# Main.net
KiCad netlist of a schematic drawn in Altium Designer
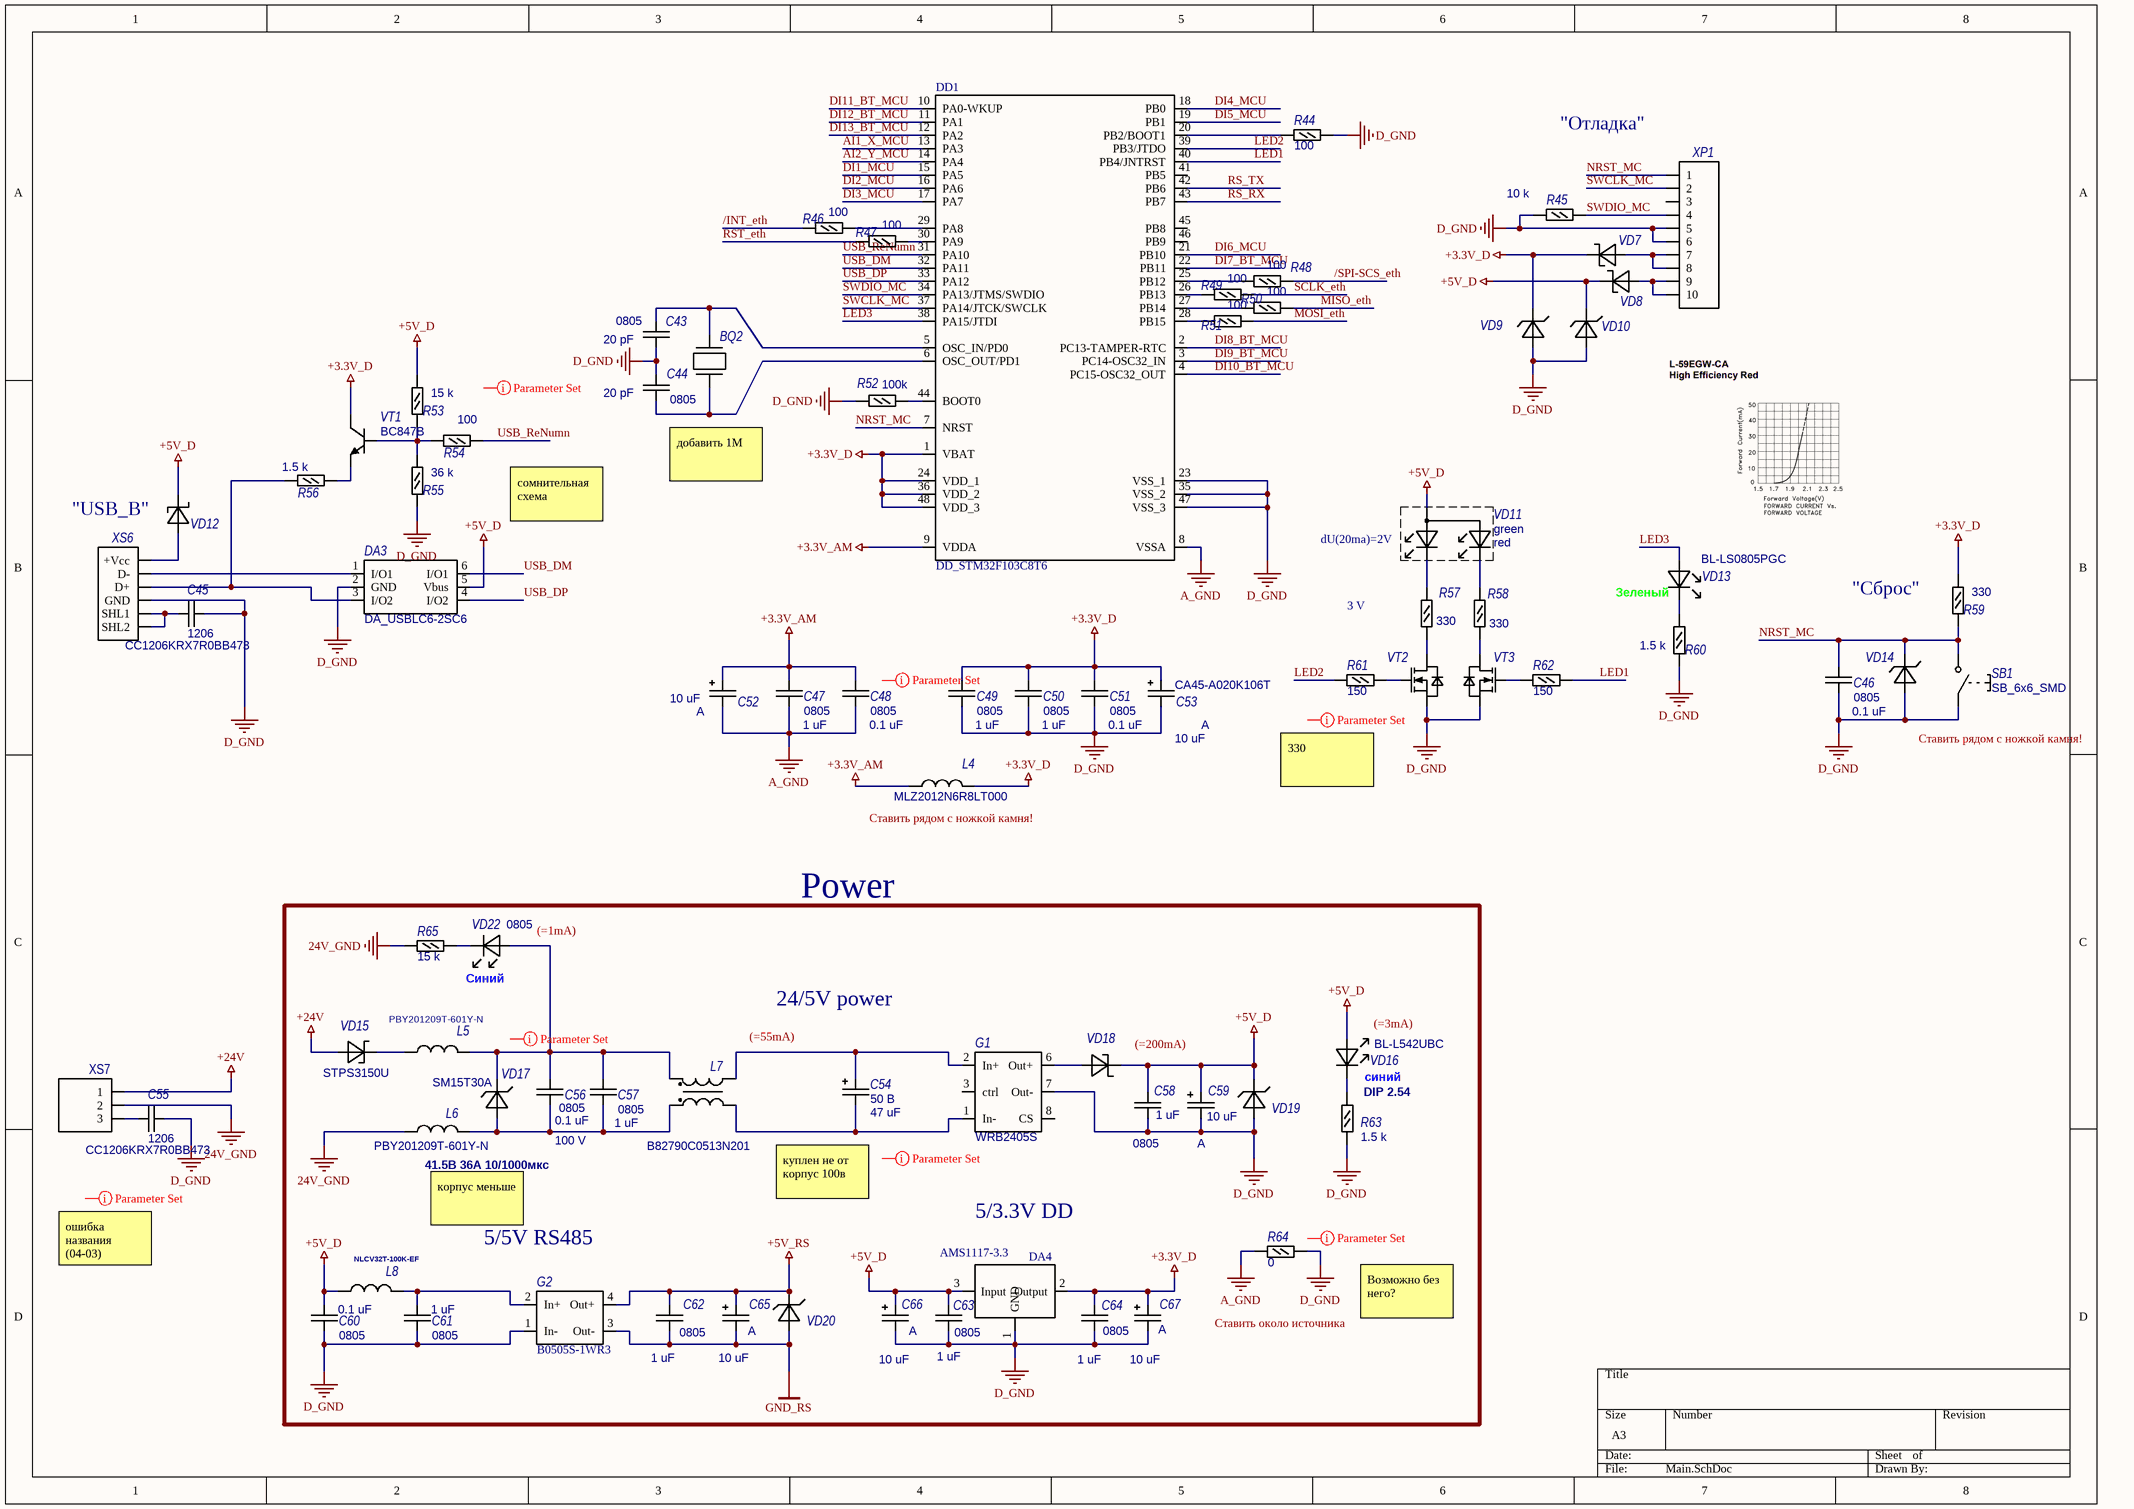
[diagram p0: Main.SchDoc]

(export (version "E")
  (design (tool "Eeschema 10.0.6"))
  (components
    (comp (ref "BQ2") (value "~") (footprint "Xtal_HC49S") (libsource (lib "Privod_A_K") (part "Xtal")))
    (comp (ref "C43")
      (value "0805")
      (footprint "CAP_0805_(2x1.25x1.3)")
      (description "Керамика")
      (fields (field (name "НОМИНАЛ") "20 pF"))
      (libsource (lib "Privod_A_K") (part "C_0805"))
    )
    (comp (ref "C44")
      (value "0805")
      (footprint "CAP_0805_(2x1.25x1.3)")
      (description "Керамика")
      (fields (field (name "НОМИНАЛ") "20 pF"))
      (libsource (lib "Privod_A_K") (part "C_0805"))
    )
    (comp (ref "C45")
      (value "1206")
      (footprint "CAP_1206_(3.2x1.6x1.5)")
      (description "Керамика")
      (fields (field (name "НАИМЕНОВАНИЕ") "CC1206KRX7R0BB473"))
      (libsource (lib "Privod_A_K") (part "C_1206"))
    )
    (comp (ref "C46")
      (value "0805")
      (footprint "CAP_0805_(2x1.25x1.3)")
      (description "Керамика")
      (fields (field (name "НОМИНАЛ") "0.1 uF"))
      (libsource (lib "Privod_A_K") (part "C_0805"))
    )
    (comp (ref "C47")
      (value "0805")
      (footprint "CAP_0805_(2x1.25x1.3)")
      (description "Керамика")
      (fields (field (name "НОМИНАЛ") "1 uF"))
      (libsource (lib "Privod_A_K") (part "C_0805"))
    )
    (comp (ref "C48")
      (value "0805")
      (footprint "CAP_0805_(2x1.25x1.3)")
      (description "Керамика")
      (fields (field (name "НОМИНАЛ") "0.1 uF"))
      (libsource (lib "Privod_A_K") (part "C_0805"))
    )
    (comp (ref "C49")
      (value "0805")
      (footprint "CAP_0805_(2x1.25x1.3)")
      (description "Керамика")
      (fields (field (name "НОМИНАЛ") "1 uF"))
      (libsource (lib "Privod_A_K") (part "C_0805"))
    )
    (comp (ref "C50")
      (value "0805")
      (footprint "CAP_0805_(2x1.25x1.3)")
      (description "Керамика")
      (fields (field (name "НОМИНАЛ") "1 uF"))
      (libsource (lib "Privod_A_K") (part "C_0805"))
    )
    (comp (ref "C51")
      (value "0805")
      (footprint "CAP_0805_(2x1.25x1.3)")
      (description "Керамика")
      (fields (field (name "НОМИНАЛ") "0.1 uF"))
      (libsource (lib "Privod_A_K") (part "C_0805"))
    )
    (comp (ref "C52")
      (value "TAN_A")
      (footprint "CAP_TAN_A")
      (description "Capacitor")
      (fields (field (name "КОРПУС") "A") (field (name "НОМИНАЛ") "10 uF"))
      (libsource (lib "Privod_A_K") (part "C+_TAN_A"))
    )
    (comp (ref "C53")
      (value "TAN_A")
      (footprint "CAP_TAN_A")
      (description "Capacitor")
      (fields
        (field (name "КОРПУС") "A")
        (field (name "НАИМЕНОВАНИЕ") "CA45-A020K106T")
        (field (name "НОМИНАЛ") "10 uF")
      )
      (libsource (lib "Privod_A_K") (part "C+_TAN_A"))
    )
    (comp (ref "C54")
      (value "K50-35")
      (footprint "CAP_EL_K50-35_(8x11.5)")
      (description "Capacitor")
      (fields (field (name "НАПРЯЖЕНИЕ") "50 В") (field (name "НОМИНАЛ") "47 uF"))
      (libsource (lib "Privod_A_K") (part "C+_K50-35_(8x11.5)"))
    )
    (comp (ref "C55")
      (value "1206")
      (footprint "CAP_1206_(3.2x1.6x1.5)")
      (description "Керамика")
      (fields (field (name "НАИМЕНОВАНИЕ") "CC1206KRX7R0BB473"))
      (libsource (lib "Privod_A_K") (part "C_1206"))
    )
    (comp (ref "C56")
      (value "0805")
      (footprint "CAP_0805_(2x1.25x1.3)")
      (description "Керамика")
      (fields (field (name "НАПРЯЖЕНИЕ") "100 V") (field (name "НОМИНАЛ") "0.1 uF"))
      (libsource (lib "Privod_A_K") (part "C_0805"))
    )
    (comp (ref "C57")
      (value "0805")
      (footprint "CAP_0805_(2x1.25x1.3)")
      (description "Керамика")
      (fields (field (name "НОМИНАЛ") "1 uF"))
      (libsource (lib "Privod_A_K") (part "C_0805"))
    )
    (comp (ref "C58")
      (value "0805")
      (footprint "CAP_0805_(2x1.25x1.3)")
      (description "Керамика")
      (fields (field (name "НОМИНАЛ") "1 uF"))
      (libsource (lib "Privod_A_K") (part "C_0805"))
    )
    (comp (ref "C59")
      (value "TAN_A")
      (footprint "CAP_TAN_A")
      (description "Capacitor")
      (fields (field (name "КОРПУС") "A") (field (name "НОМИНАЛ") "10 uF"))
      (libsource (lib "Privod_A_K") (part "C+_TAN_A"))
    )
    (comp (ref "C60")
      (value "0805")
      (footprint "CAP_0805_(2x1.25x1.3)")
      (description "Керамика")
      (fields (field (name "НОМИНАЛ") "0.1 uF"))
      (libsource (lib "Privod_A_K") (part "C_0805"))
    )
    (comp (ref "C61")
      (value "0805")
      (footprint "CAP_0805_(2x1.25x1.3)")
      (description "Керамика")
      (fields (field (name "НОМИНАЛ") "1 uF"))
      (libsource (lib "Privod_A_K") (part "C_0805"))
    )
    (comp (ref "C62")
      (value "0805")
      (footprint "CAP_0805_(2x1.25x1.3)")
      (description "Керамика")
      (fields (field (name "НОМИНАЛ") "1 uF"))
      (libsource (lib "Privod_A_K") (part "C_0805"))
    )
    (comp (ref "C63")
      (value "0805")
      (footprint "CAP_0805_(2x1.25x1.3)")
      (description "Керамика")
      (fields (field (name "НОМИНАЛ") "1 uF"))
      (libsource (lib "Privod_A_K") (part "C_0805"))
    )
    (comp (ref "C64")
      (value "0805")
      (footprint "CAP_0805_(2x1.25x1.3)")
      (description "Керамика")
      (fields (field (name "НОМИНАЛ") "1 uF"))
      (libsource (lib "Privod_A_K") (part "C_0805"))
    )
    (comp (ref "C65")
      (value "TAN_A")
      (footprint "CAP_TAN_A")
      (description "Capacitor")
      (fields (field (name "КОРПУС") "A") (field (name "НОМИНАЛ") "10 uF"))
      (libsource (lib "Privod_A_K") (part "C+_TAN_A"))
    )
    (comp (ref "C66")
      (value "TAN_A")
      (footprint "CAP_TAN_A")
      (description "Capacitor")
      (fields (field (name "КОРПУС") "A") (field (name "НОМИНАЛ") "10 uF"))
      (libsource (lib "Privod_A_K") (part "C+_TAN_A"))
    )
    (comp (ref "C67")
      (value "TAN_A")
      (footprint "CAP_TAN_A")
      (description "Capacitor")
      (fields (field (name "КОРПУС") "A") (field (name "НОМИНАЛ") "10 uF"))
      (libsource (lib "Privod_A_K") (part "C+_TAN_A"))
    )
    (comp (ref "DA3")
      (value "DA_USBLC6-2SC6")
      (footprint "SOT-23-6L")
      (description "USB ESD protector SOT23-6")
      (libsource (lib "Privod_A_K") (part "DA_USBLC6-2SC6"))
    )
    (comp (ref "DA4")
      (value "AMS1117-3.3")
      (footprint "SOT-223_Dupl")
      (description "0.8A Low Dropout Voltage Regulator       SOT 223")
      (libsource (lib "Privod_A_K") (part "DA_AMS1117-3.3"))
    )
    (comp (ref "DD1")
      (value "DD_STM32F103C8T6")
      (footprint "LQFP_48")
      (description "STM32 ARM-based 32-bit MCU with 128 Kbytes Flash, 48-pin LQFP, Industrial Temperature")
      (fields (field (name "PUBLISHER") "Altium Limited"))
      (libsource (lib "Privod_A_K") (part "DD_STM32F103C8T6"))
    )
    (comp (ref "G1")
      (value "WRB2405S")
      (footprint "WRB2405S(SIP-8) - duplicate")
      (description "DC/DC")
      (libsource (lib "Privod_A_K") (part "G_WRB2405S-1WR2"))
    )
    (comp (ref "G2")
      (value "AM1S-Z")
      (footprint "AM1S-Z")
      (description "DC/DC")
      (fields (field (name "НАИМЕНОВАНИЕ") "B0505S-1WR3"))
      (libsource (lib "Privod_A_K") (part "G_AM1S-Z"))
    )
    (comp (ref "L4")
      (value "PBY201209T-601Y-N")
      (footprint "L_0805")
      (description "L")
      (fields (field (name "НАИМЕНОВАНИЕ") "MLZ2012N6R8LT000"))
      (libsource (lib "Privod_A_K") (part "L_PBY201209T-601Y-N"))
    )
    (comp (ref "L5")
      (value "PBY201209T-601Y-N")
      (footprint "L_0805")
      (description "L")
      (libsource (lib "Privod_A_K") (part "L_PBY201209T-601Y-N"))
    )
    (comp (ref "L6")
      (value "PBY201209T-601Y-N")
      (footprint "L_0805")
      (description "L")
      (libsource (lib "Privod_A_K") (part "L_PBY201209T-601Y-N"))
    )
    (comp (ref "L7")
      (value "B82790")
      (footprint "B82790")
      (description "L")
      (fields (field (name "НАИМЕНОВАНИЕ") "B82790C0513N201"))
      (libsource (lib "Privod_A_K") (part "L_B82790"))
    )
    (comp (ref "L8")
      (value "SRN3015")
      (footprint "L_SRN3015")
      (description "L")
      (fields (field (name "НАИМЕНОВАНИЕ") "NLCV32T-100K-EF"))
      (libsource (lib "Privod_A_K") (part "L_SRN3015"))
    )
    (comp (ref "R44")
      (value "0805")
      (footprint "RES_0805_(2x1.2x0.45)_0.125Вт")
      (description "Resistor")
      (fields (field (name "НОМИНАЛ") "100"))
      (libsource (lib "") (part "R_0805_2"))
    )
    (comp (ref "R45")
      (value "0805")
      (footprint "RES_0805_(2x1.2x0.45)_0.125Вт")
      (description "Resistor")
      (fields (field (name "НОМИНАЛ") "10 k"))
      (libsource (lib "") (part "R_0805_2"))
    )
    (comp (ref "R46")
      (value "0805")
      (footprint "RES_0805_(2x1.2x0.45)_0.125Вт")
      (description "Resistor")
      (fields (field (name "НОМИНАЛ") "100"))
      (libsource (lib "") (part "R_0805_2"))
    )
    (comp (ref "R47")
      (value "0805")
      (footprint "RES_0805_(2x1.2x0.45)_0.125Вт")
      (description "Resistor")
      (fields (field (name "НОМИНАЛ") "100"))
      (libsource (lib "") (part "R_0805_2"))
    )
    (comp (ref "R48")
      (value "0805")
      (footprint "RES_0805_(2x1.2x0.45)_0.125Вт")
      (description "Resistor")
      (fields (field (name "НОМИНАЛ") "100"))
      (libsource (lib "") (part "R_0805_2"))
    )
    (comp (ref "R49")
      (value "0805")
      (footprint "RES_0805_(2x1.2x0.45)_0.125Вт")
      (description "Resistor")
      (fields (field (name "НОМИНАЛ") "100"))
      (libsource (lib "") (part "R_0805_2"))
    )
    (comp (ref "R50")
      (value "0805")
      (footprint "RES_0805_(2x1.2x0.45)_0.125Вт")
      (description "Resistor")
      (fields (field (name "НОМИНАЛ") "100"))
      (libsource (lib "") (part "R_0805_2"))
    )
    (comp (ref "R51")
      (value "0805")
      (footprint "RES_0805_(2x1.2x0.45)_0.125Вт")
      (description "Resistor")
      (fields (field (name "НОМИНАЛ") "100"))
      (libsource (lib "") (part "R_0805_2"))
    )
    (comp (ref "R52")
      (value "0805")
      (footprint "RES_0805_(2x1.2x0.45)_0.125Вт")
      (description "Resistor")
      (fields (field (name "НОМИНАЛ") "100k"))
      (libsource (lib "") (part "R_0805_2"))
    )
    (comp (ref "R53")
      (value "0805")
      (footprint "RES_0805_(2x1.2x0.45)_0.125Вт")
      (description "Resistor")
      (fields (field (name "НОМИНАЛ") "15 k"))
      (libsource (lib "") (part "R_0805_1"))
    )
    (comp (ref "R54")
      (value "0805")
      (footprint "RES_0805_(2x1.2x0.45)_0.125Вт")
      (description "Resistor")
      (fields (field (name "НОМИНАЛ") "100"))
      (libsource (lib "") (part "R_0805_2"))
    )
    (comp (ref "R55")
      (value "0805")
      (footprint "RES_0805_(2x1.2x0.45)_0.125Вт")
      (description "Resistor")
      (fields (field (name "НОМИНАЛ") "36 k"))
      (libsource (lib "") (part "R_0805_1"))
    )
    (comp (ref "R56")
      (value "0805")
      (footprint "RES_0805_(2x1.2x0.45)_0.125Вт")
      (description "Resistor")
      (fields (field (name "НОМИНАЛ") "1.5 k"))
      (libsource (lib "") (part "R_0805_2"))
    )
    (comp (ref "R57")
      (value "0805")
      (footprint "RES_0805_(2x1.2x0.45)_0.125Вт")
      (description "Resistor")
      (fields (field (name "НОМИНАЛ") "330"))
      (libsource (lib "") (part "R_0805_3"))
    )
    (comp (ref "R58")
      (value "0805")
      (footprint "RES_0805_(2x1.2x0.45)_0.125Вт")
      (description "Resistor")
      (fields (field (name "НОМИНАЛ") "330"))
      (libsource (lib "") (part "R_0805_3"))
    )
    (comp (ref "R59")
      (value "0805")
      (footprint "RES_0805_(2x1.2x0.45)_0.125Вт")
      (description "Resistor")
      (fields (field (name "НОМИНАЛ") "330"))
      (libsource (lib "") (part "R_0805_3"))
    )
    (comp (ref "R60")
      (value "0805")
      (footprint "RES_0805_(2x1.2x0.45)_0.125Вт")
      (description "Resistor")
      (fields (field (name "НОМИНАЛ") "1.5 k"))
      (libsource (lib "") (part "R_0805_1"))
    )
    (comp (ref "R61")
      (value "0805")
      (footprint "RES_0805_(2x1.2x0.45)_0.125Вт")
      (description "Resistor")
      (fields (field (name "НОМИНАЛ") "150"))
      (libsource (lib "Privod_A_K") (part "R_0805"))
    )
    (comp (ref "R62")
      (value "0805")
      (footprint "RES_0805_(2x1.2x0.45)_0.125Вт")
      (description "Resistor")
      (fields (field (name "НОМИНАЛ") "150"))
      (libsource (lib "Privod_A_K") (part "R_0805"))
    )
    (comp (ref "R63")
      (value "0805")
      (footprint "RES_0805_(2x1.2x0.45)_0.125Вт")
      (description "Resistor")
      (fields (field (name "НОМИНАЛ") "1.5 k"))
      (libsource (lib "") (part "R_0805_1"))
    )
    (comp (ref "R64")
      (value "0805")
      (footprint "RES_0805_(2x1.2x0.45)_0.125Вт")
      (description "Resistor")
      (fields (field (name "НОМИНАЛ") "0"))
      (libsource (lib "Privod_A_K") (part "R_0805"))
    )
    (comp (ref "R65")
      (value "0805")
      (footprint "RES_0805_(2x1.2x0.45)_0.125Вт")
      (description "Resistor")
      (fields (field (name "НОМИНАЛ") "15 k"))
      (libsource (lib "Privod_A_K") (part "R_0805"))
    )
    (comp (ref "SB1")
      (value "SB_6x6_SMD")
      (footprint "SB_6x6_SMD")
      (libsource (lib "Privod_A_K") (part "SB_6x6_SMD"))
    )
    (comp (ref "VD7")
      (value "VD_SH_SMA")
      (footprint "VD_SMA_(Do-214AC)")
      (description "Sh_Diode")
      (libsource (lib "Privod_A_K") (part "VD_SH_SMA"))
    )
    (comp (ref "VD8")
      (value "VD_SH_SMA")
      (footprint "VD_SMA_(Do-214AC)")
      (description "Sh_Diode")
      (libsource (lib "Privod_A_K") (part "VD_SH_SMA"))
    )
    (comp (ref "VD9")
      (value "ESD")
      (footprint "VD_SOD523")
      (description "Защитный диод")
      (libsource (lib "Privod_A_K") (part "VD_ESD"))
    )
    (comp (ref "VD10")
      (value "ESD")
      (footprint "VD_SOD523")
      (description "Защитный диод")
      (libsource (lib "Privod_A_K") (part "VD_ESD"))
    )
    (comp (ref "VD11")
      (value "VD_Ledx2_dip")
      (footprint "VD_LEDsx2")
      (fields (field (name "ТИП") "green") (field (name "ПРИМЕЧАНИЯ") "red"))
      (libsource (lib "Privod_A_K") (part "VD_Ledx2_dip"))
    )
    (comp (ref "VD12")
      (value "VD_SH_SMA")
      (footprint "VD_SMA_(Do-214AC)")
      (description "Sh_Diode")
      (libsource (lib "Privod_A_K") (part "VD_SH_SMA"))
    )
    (comp (ref "VD13")
      (value "VD_Led_0805")
      (footprint "led_0805")
      (fields (field (name "НАИМЕНОВАНИЕ") "BL-LS0805PGC") (field (name "ПРИМЕЧАНИЯ") "Зеленый"))
      (libsource (lib "Privod_A_K") (part "VD_Led_0805"))
    )
    (comp (ref "VD14")
      (value "ESD")
      (footprint "VD_SOD523")
      (description "Защитный диод")
      (libsource (lib "Privod_A_K") (part "VD_ESD"))
    )
    (comp (ref "VD15")
      (value "STPS3150U")
      (footprint "VD_SMB_(Do-214AA)")
      (description "Диод Шоттки 150В 3А [SMB]")
      (libsource (lib "Privod_A_K") (part "VD_STPS3150U"))
    )
    (comp (ref "VD16")
      (value "VD_Led")
      (footprint "VD_LED_dip")
      (fields
        (field (name "КОРПУС") "DIP 2.54")
        (field (name "НАИМЕНОВАНИЕ") "BL-L542UBC")
        (field (name "ПРИМЕЧАНИЯ") "синий")
      )
      (libsource (lib "Privod_A_K") (part "VD_Led"))
    )
    (comp (ref "VD17")
      (value "SM15T30A")
      (footprint "VD_SMC_(Do-214AB)")
      (description "Защитный диод 48В")
      (fields (field (name "НОМИНАЛ") " 41.5В 36А 10/1000мкс"))
      (libsource (lib "Privod_A_K") (part "VD_SMCJ48A"))
    )
    (comp (ref "VD18")
      (value "VD_SH_SMA")
      (footprint "VD_SMA_(Do-214AC)")
      (description "Sh_Diode")
      (libsource (lib "Privod_A_K") (part "VD_SH_SMA"))
    )
    (comp (ref "VD19")
      (value "VD_SMA")
      (footprint "VD_SMA_(Do-214AC)")
      (description "Diode")
      (libsource (lib "Privod_A_K") (part "VD_SMA"))
    )
    (comp (ref "VD20")
      (value "VD_SMA")
      (footprint "VD_SMA_(Do-214AC)")
      (description "Diode")
      (libsource (lib "Privod_A_K") (part "VD_SMA"))
    )
    (comp (ref "VD22")
      (value "VD_Led_0805")
      (footprint "led_0805")
      (fields (field (name "КОРПУС") "0805") (field (name "ПРИМЕЧАНИЯ") "Синий"))
      (libsource (lib "Privod_A_K") (part "VD_Led_0805"))
    )
    (comp (ref "VT1")
      (value "BC847B")
      (footprint "SOT-23")
      (description "NPN Bipolar Transistor")
      (libsource (lib "Privod_A_K") (part "VT_BC847B"))
    )
    (comp (ref "VT2")
      (value "VT_IRLML0040TRPBF")
      (footprint "SOT-23")
      (description "N Mosfet 3.6A")
      (libsource (lib "Privod_A_K") (part "VT_IRLML0040TRPBF"))
    )
    (comp (ref "VT3")
      (value "VT_IRLML0040TRPBF")
      (footprint "SOT-23")
      (description "N Mosfet 3.6A")
      (libsource (lib "Privod_A_K") (part "VT_IRLML0040TRPBF"))
    )
    (comp (ref "XP1")
      (value "XP_5x2_V")
      (footprint "XP_5x2_PIN_V")
      (libsource (lib "Privod_A_K") (part "XP_5x2_V"))
    )
    (comp (ref "XS6")
      (value "XS_USB_B")
      (footprint "XS_USBB")
      (libsource (lib "Privod_A_K") (part "XS_USB_B"))
    )
    (comp (ref "XS7")
      (value "XS_3_pin_3.8mm")
      (footprint "XS_3_Pin _3.8mm")
      (libsource (lib "Privod_A_K") (part "XS_3_pin_3.8mm"))
    )
  )
  (nets
    (net (code "1") (name "+3.3V_AM") (class "Default")
      (node (ref "C47") (pin "2") (pinfunction "2_2") (pintype "passive"))
      (node (ref "C48") (pin "2") (pinfunction "2_2") (pintype "passive"))
      (node (ref "C52") (pin "1") (pinfunction "1_1") (pintype "passive"))
      (node (ref "DD1") (pin "9") (pinfunction "VDDA_9") (pintype "passive"))
      (node (ref "L4") (pin "1") (pinfunction "1_1") (pintype "passive"))
    )
    (net (code "2") (name "+3.3V_D") (class "Default")
      (node (ref "C49") (pin "2") (pinfunction "2_2") (pintype "passive"))
      (node (ref "C50") (pin "2") (pinfunction "2_2") (pintype "passive"))
      (node (ref "C51") (pin "2") (pinfunction "2_2") (pintype "passive"))
      (node (ref "C53") (pin "1") (pinfunction "1_1") (pintype "passive"))
      (node (ref "C64") (pin "2") (pinfunction "2_2") (pintype "passive"))
      (node (ref "C67") (pin "1") (pinfunction "1_1") (pintype "passive"))
      (node (ref "DA4") (pin "2") (pinfunction "Output_2") (pintype "passive"))
      (node (ref "DD1") (pin "1") (pinfunction "VBAT_1") (pintype "passive"))
      (node (ref "DD1") (pin "24") (pinfunction "VDD_1_24") (pintype "passive"))
      (node (ref "DD1") (pin "36") (pinfunction "VDD_2_36") (pintype "passive"))
      (node (ref "DD1") (pin "48") (pinfunction "VDD_3_48") (pintype "passive"))
      (node (ref "L4") (pin "2") (pinfunction "2_2") (pintype "passive"))
      (node (ref "R59") (pin "1") (pinfunction "1_1") (pintype "passive"))
      (node (ref "VD7") (pin "2") (pinfunction "K_2") (pintype "passive"))
      (node (ref "VD9") (pin "2") (pinfunction "K_2") (pintype "passive"))
      (node (ref "VT1") (pin "3") (pinfunction "C_3") (pintype "passive"))
    )
    (net (code "3") (name "+5V_D") (class "Default")
      (node (ref "C58") (pin "2") (pinfunction "2_2") (pintype "passive"))
      (node (ref "C59") (pin "1") (pinfunction "1_1") (pintype "passive"))
      (node (ref "C60") (pin "2") (pinfunction "2_2") (pintype "passive"))
      (node (ref "C63") (pin "2") (pinfunction "2_2") (pintype "passive"))
      (node (ref "C66") (pin "1") (pinfunction "1_1") (pintype "passive"))
      (node (ref "DA3") (pin "5") (pinfunction "Vbus_5") (pintype "passive"))
      (node (ref "DA4") (pin "3") (pinfunction "Input_3") (pintype "passive"))
      (node (ref "L8") (pin "1") (pinfunction "1_1") (pintype "passive"))
      (node (ref "R53") (pin "2") (pinfunction "2_2") (pintype "passive"))
      (node (ref "VD10") (pin "2") (pinfunction "K_2") (pintype "passive"))
      (node (ref "VD11") (pin "2") (pinfunction "A_2") (pintype "passive"))
      (node (ref "VD12") (pin "2") (pinfunction "K_2") (pintype "passive"))
      (node (ref "VD16") (pin "1") (pinfunction "A_1") (pintype "passive"))
      (node (ref "VD18") (pin "2") (pinfunction "K_2") (pintype "passive"))
      (node (ref "VD19") (pin "2") (pinfunction "K_2") (pintype "passive"))
      (node (ref "VD8") (pin "2") (pinfunction "K_2") (pintype "passive"))
    )
    (net (code "4") (name "+5V_RS") (class "Default")
      (node (ref "C62") (pin "2") (pinfunction "2_2") (pintype "passive"))
      (node (ref "C65") (pin "1") (pinfunction "1_1") (pintype "passive"))
      (node (ref "G2") (pin "4") (pinfunction "Out+_4") (pintype "passive"))
      (node (ref "VD20") (pin "2") (pinfunction "K_2") (pintype "passive"))
    )
    (net (code "5") (name "+24V") (class "Default")
      (node (ref "VD15") (pin "1") (pinfunction "A_1") (pintype "passive"))
      (node (ref "XS7") (pin "1") (pinfunction "1_1") (pintype "passive"))
    )
    (net (code "6") (name "/AI1_X_MCU") (class "Default")
      (node (ref "DD1") (pin "13") (pinfunction "PA3_13") (pintype "passive"))
    )
    (net (code "7") (name "/AI2_Y_MCU") (class "Default")
      (node (ref "DD1") (pin "14") (pinfunction "PA4_14") (pintype "passive"))
    )
    (net (code "8") (name "/DI1_MCU") (class "Default")
      (node (ref "DD1") (pin "15") (pinfunction "PA5_15") (pintype "passive"))
    )
    (net (code "9") (name "/DI2_MCU") (class "Default")
      (node (ref "DD1") (pin "16") (pinfunction "PA6_16") (pintype "passive"))
    )
    (net (code "10") (name "/DI3_MCU") (class "Default")
      (node (ref "DD1") (pin "17") (pinfunction "PA7_17") (pintype "passive"))
    )
    (net (code "11") (name "/DI4_MCU") (class "Default")
      (node (ref "DD1") (pin "18") (pinfunction "PB0_18") (pintype "passive"))
    )
    (net (code "12") (name "/DI5_MCU") (class "Default")
      (node (ref "DD1") (pin "19") (pinfunction "PB1_19") (pintype "passive"))
    )
    (net (code "13") (name "/DI6_MCU") (class "Default")
      (node (ref "DD1") (pin "21") (pinfunction "PB10_21") (pintype "passive"))
    )
    (net (code "14") (name "/DI7_BT_MCU") (class "Default")
      (node (ref "DD1") (pin "22") (pinfunction "PB11_22") (pintype "passive"))
    )
    (net (code "15") (name "/DI8_BT_MCU") (class "Default")
      (node (ref "DD1") (pin "2") (pinfunction "PC13-TAMPER-RTC_2") (pintype "passive"))
    )
    (net (code "16") (name "/DI9_BT_MCU") (class "Default")
      (node (ref "DD1") (pin "3") (pinfunction "PC14-OSC32_IN_3") (pintype "passive"))
    )
    (net (code "17") (name "/DI10_BT_MCU") (class "Default")
      (node (ref "DD1") (pin "4") (pinfunction "PC15-OSC32_OUT_4") (pintype "passive"))
    )
    (net (code "18") (name "/DI11_BT_MCU") (class "Default")
      (node (ref "DD1") (pin "10") (pinfunction "PA0-WKUP_10") (pintype "passive"))
    )
    (net (code "19") (name "/DI12_BT_MCU") (class "Default")
      (node (ref "DD1") (pin "11") (pinfunction "PA1_11") (pintype "passive"))
    )
    (net (code "20") (name "/DI13_BT_MCU") (class "Default")
      (node (ref "DD1") (pin "12") (pinfunction "PA2_12") (pintype "passive"))
    )
    (net (code "21") (name "/LED1") (class "Default")
      (node (ref "DD1") (pin "40") (pinfunction "PB4/JNTRST_40") (pintype "passive"))
      (node (ref "R62") (pin "2") (pinfunction "2_2") (pintype "passive"))
    )
    (net (code "22") (name "/LED2") (class "Default")
      (node (ref "DD1") (pin "39") (pinfunction "PB3/JTDO_39") (pintype "passive"))
      (node (ref "R61") (pin "1") (pinfunction "1_1") (pintype "passive"))
    )
    (net (code "23") (name "/LED3") (class "Default")
      (node (ref "DD1") (pin "38") (pinfunction "PA15/JTDI_38") (pintype "passive"))
      (node (ref "VD13") (pin "1") (pinfunction "A_1") (pintype "passive"))
    )
    (net (code "24") (name "/MISO_eth") (class "Default")
      (node (ref "R50") (pin "1") (pinfunction "1_1") (pintype "passive"))
    )
    (net (code "25") (name "/MOSI_eth") (class "Default")
      (node (ref "R51") (pin "1") (pinfunction "1_1") (pintype "passive"))
    )
    (net (code "26") (name "/NRST_MC") (class "Default")
      (node (ref "C46") (pin "2") (pinfunction "2_2") (pintype "passive"))
      (node (ref "DD1") (pin "7") (pinfunction "NRST_7") (pintype "passive"))
      (node (ref "R59") (pin "2") (pinfunction "2_2") (pintype "passive"))
      (node (ref "SB1") (pin "2") (pinfunction "2_2") (pintype "passive"))
      (node (ref "VD14") (pin "2") (pinfunction "K_2") (pintype "passive"))
      (node (ref "XP1") (pin "1") (pinfunction "1_1") (pintype "passive"))
    )
    (net (code "27") (name "/RST_eth") (class "Default")
      (node (ref "R47") (pin "2") (pinfunction "2_2") (pintype "passive"))
    )
    (net (code "28") (name "/RS_RX") (class "Default")
      (node (ref "DD1") (pin "43") (pinfunction "PB7_43") (pintype "passive"))
    )
    (net (code "29") (name "/RS_TX") (class "Default")
      (node (ref "DD1") (pin "42") (pinfunction "PB6_42") (pintype "passive"))
    )
    (net (code "30") (name "/SCLK_eth") (class "Default")
      (node (ref "R49") (pin "1") (pinfunction "1_1") (pintype "passive"))
    )
    (net (code "31") (name "/SWCLK_MC") (class "Default")
      (node (ref "DD1") (pin "37") (pinfunction "PA14/JTCK/SWCLK_37") (pintype "passive"))
      (node (ref "XP1") (pin "2") (pinfunction "2_2") (pintype "passive"))
    )
    (net (code "32") (name "/SWDIO_MC") (class "Default")
      (node (ref "DD1") (pin "34") (pinfunction "PA13/JTMS/SWDIO_34") (pintype "passive"))
      (node (ref "R45") (pin "1") (pinfunction "1_1") (pintype "passive"))
      (node (ref "XP1") (pin "4") (pinfunction "4_4") (pintype "passive"))
    )
    (net (code "33") (name "/USB_DM") (class "Default")
      (node (ref "DA3") (pin "6") (pinfunction "I/O1_6") (pintype "passive"))
      (node (ref "DD1") (pin "32") (pinfunction "PA11_32") (pintype "passive"))
    )
    (net (code "34") (name "/USB_DP") (class "Default")
      (node (ref "DA3") (pin "4") (pinfunction "I/O2_4") (pintype "passive"))
      (node (ref "DD1") (pin "33") (pinfunction "PA12_33") (pintype "passive"))
    )
    (net (code "35") (name "/USB_ReNumn") (class "Default")
      (node (ref "DD1") (pin "31") (pinfunction "PA10_31") (pintype "passive"))
      (node (ref "R54") (pin "1") (pinfunction "1_1") (pintype "passive"))
    )
    (net (code "36") (name "/{slash}INT_eth") (class "Default")
      (node (ref "R46") (pin "2") (pinfunction "2_2") (pintype "passive"))
    )
    (net (code "37") (name "/{slash}SPI-SCS_eth") (class "Default")
      (node (ref "R48") (pin "1") (pinfunction "1_1") (pintype "passive"))
    )
    (net (code "38") (name "24V_GND") (class "Default")
      (node (ref "L6") (pin "1") (pinfunction "1_1") (pintype "passive"))
      (node (ref "R65") (pin "1") (pinfunction "1_1") (pintype "passive"))
      (node (ref "XS7") (pin "2") (pinfunction "2_2") (pintype "passive"))
    )
    (net (code "39") (name "A_GND") (class "Default")
      (node (ref "C47") (pin "1") (pinfunction "1_1") (pintype "passive"))
      (node (ref "C48") (pin "1") (pinfunction "1_1") (pintype "passive"))
      (node (ref "C52") (pin "2") (pinfunction "2_2") (pintype "passive"))
      (node (ref "DD1") (pin "8") (pinfunction "VSSA_8") (pintype "passive"))
      (node (ref "R64") (pin "1") (pinfunction "1_1") (pintype "passive"))
    )
    (net (code "40") (name "D_GND") (class "Default")
      (node (ref "C43") (pin "1") (pinfunction "1_1") (pintype "passive"))
      (node (ref "C44") (pin "2") (pinfunction "2_2") (pintype "passive"))
      (node (ref "C45") (pin "2") (pinfunction "2_2") (pintype "passive"))
      (node (ref "C46") (pin "1") (pinfunction "1_1") (pintype "passive"))
      (node (ref "C49") (pin "1") (pinfunction "1_1") (pintype "passive"))
      (node (ref "C50") (pin "1") (pinfunction "1_1") (pintype "passive"))
      (node (ref "C51") (pin "1") (pinfunction "1_1") (pintype "passive"))
      (node (ref "C53") (pin "2") (pinfunction "2_2") (pintype "passive"))
      (node (ref "C55") (pin "2") (pinfunction "2_2") (pintype "passive"))
      (node (ref "C58") (pin "1") (pinfunction "1_1") (pintype "passive"))
      (node (ref "C59") (pin "2") (pinfunction "2_2") (pintype "passive"))
      (node (ref "C60") (pin "1") (pinfunction "1_1") (pintype "passive"))
      (node (ref "C61") (pin "1") (pinfunction "1_1") (pintype "passive"))
      (node (ref "C63") (pin "1") (pinfunction "1_1") (pintype "passive"))
      (node (ref "C64") (pin "1") (pinfunction "1_1") (pintype "passive"))
      (node (ref "C66") (pin "2") (pinfunction "2_2") (pintype "passive"))
      (node (ref "C67") (pin "2") (pinfunction "2_2") (pintype "passive"))
      (node (ref "DA3") (pin "2") (pinfunction "GND_2") (pintype "passive"))
      (node (ref "DA4") (pin "1") (pinfunction "GND_1") (pintype "passive"))
      (node (ref "DD1") (pin "23") (pinfunction "VSS_1_23") (pintype "passive"))
      (node (ref "DD1") (pin "35") (pinfunction "VSS_2_35") (pintype "passive"))
      (node (ref "DD1") (pin "47") (pinfunction "VSS_3_47") (pintype "passive"))
      (node (ref "G1") (pin "7") (pinfunction "Out-_7") (pintype "passive"))
      (node (ref "G2") (pin "1") (pinfunction "In-_1") (pintype "passive"))
      (node (ref "R44") (pin "1") (pinfunction "1_1") (pintype "passive"))
      (node (ref "R45") (pin "2") (pinfunction "2_2") (pintype "passive"))
      (node (ref "R52") (pin "2") (pinfunction "2_2") (pintype "passive"))
      (node (ref "R55") (pin "1") (pinfunction "1_1") (pintype "passive"))
      (node (ref "R60") (pin "1") (pinfunction "1_1") (pintype "passive"))
      (node (ref "R63") (pin "1") (pinfunction "1_1") (pintype "passive"))
      (node (ref "R64") (pin "2") (pinfunction "2_2") (pintype "passive"))
      (node (ref "SB1") (pin "1") (pinfunction "1_1") (pintype "passive"))
      (node (ref "VD10") (pin "1") (pinfunction "A_1") (pintype "passive"))
      (node (ref "VD14") (pin "1") (pinfunction "A_1") (pintype "passive"))
      (node (ref "VD19") (pin "1") (pinfunction "A_1") (pintype "passive"))
      (node (ref "VD9") (pin "1") (pinfunction "A_1") (pintype "passive"))
      (node (ref "VT2") (pin "2") (pinfunction "S_2") (pintype "passive"))
      (node (ref "VT3") (pin "2") (pinfunction "S_2") (pintype "passive"))
      (node (ref "XP1") (pin "5") (pinfunction "5_5") (pintype "passive"))
      (node (ref "XP1") (pin "6") (pinfunction "6_6") (pintype "passive"))
      (node (ref "XS6") (pin "4") (pinfunction "GND_4") (pintype "passive"))
    )
    (net (code "41") (name "GND_RS") (class "Default")
      (node (ref "C62") (pin "1") (pinfunction "1_1") (pintype "passive"))
      (node (ref "C65") (pin "2") (pinfunction "2_2") (pintype "passive"))
      (node (ref "G2") (pin "3") (pinfunction "Out-_3") (pintype "passive"))
      (node (ref "VD20") (pin "1") (pinfunction "A_1") (pintype "passive"))
    )
    (net (code "42") (name "Net-(C55-Pad1)") (class "Default")
      (node (ref "C55") (pin "1") (pinfunction "1_1") (pintype "passive"))
      (node (ref "XS7") (pin "3") (pinfunction "3_3") (pintype "passive"))
    )
    (net (code "43") (name "Net-(DD1-BOOT0)") (class "Default")
      (node (ref "DD1") (pin "44") (pinfunction "BOOT0_44") (pintype "passive"))
      (node (ref "R52") (pin "1") (pinfunction "1_1") (pintype "passive"))
    )
    (net (code "44") (name "Net-(DD1-OSC_IN{slash}PD0)") (class "Default")
      (node (ref "BQ2") (pin "2") (pinfunction "2_2") (pintype "passive"))
      (node (ref "C43") (pin "2") (pinfunction "2_2") (pintype "passive"))
      (node (ref "DD1") (pin "5") (pinfunction "OSC_IN/PD0_5") (pintype "passive"))
    )
    (net (code "45") (name "Net-(DD1-OSC_OUT{slash}PD1)") (class "Default")
      (node (ref "BQ2") (pin "1") (pinfunction "1_1") (pintype "passive"))
      (node (ref "C44") (pin "1") (pinfunction "1_1") (pintype "passive"))
      (node (ref "DD1") (pin "6") (pinfunction "OSC_OUT/PD1_6") (pintype "passive"))
    )
    (net (code "46") (name "Net-(DD1-PA8)") (class "Default")
      (node (ref "DD1") (pin "29") (pinfunction "PA8_29") (pintype "passive"))
      (node (ref "R46") (pin "1") (pinfunction "1_1") (pintype "passive"))
    )
    (net (code "47") (name "Net-(DD1-PA9)") (class "Default")
      (node (ref "DD1") (pin "30") (pinfunction "PA9_30") (pintype "passive"))
      (node (ref "R47") (pin "1") (pinfunction "1_1") (pintype "passive"))
    )
    (net (code "48") (name "Net-(DD1-PB2{slash}BOOT1)") (class "Default")
      (node (ref "DD1") (pin "20") (pinfunction "PB2/BOOT1_20") (pintype "passive"))
      (node (ref "R44") (pin "2") (pinfunction "2_2") (pintype "passive"))
    )
    (net (code "49") (name "Net-(DD1-PB12)") (class "Default")
      (node (ref "DD1") (pin "25") (pinfunction "PB12_25") (pintype "passive"))
      (node (ref "R48") (pin "2") (pinfunction "2_2") (pintype "passive"))
    )
    (net (code "50") (name "Net-(DD1-PB13)") (class "Default")
      (node (ref "DD1") (pin "26") (pinfunction "PB13_26") (pintype "passive"))
      (node (ref "R49") (pin "2") (pinfunction "2_2") (pintype "passive"))
    )
    (net (code "51") (name "Net-(DD1-PB14)") (class "Default")
      (node (ref "DD1") (pin "27") (pinfunction "PB14_27") (pintype "passive"))
      (node (ref "R50") (pin "2") (pinfunction "2_2") (pintype "passive"))
    )
    (net (code "52") (name "Net-(DD1-PB15)") (class "Default")
      (node (ref "DD1") (pin "28") (pinfunction "PB15_28") (pintype "passive"))
      (node (ref "R51") (pin "2") (pinfunction "2_2") (pintype "passive"))
    )
    (net (code "53") (name "Net-(G1-In+)") (class "Default")
      (node (ref "C54") (pin "1") (pinfunction "1_1") (pintype "passive"))
      (node (ref "G1") (pin "2") (pinfunction "In+_2") (pintype "passive"))
      (node (ref "L7") (pin "4") (pinfunction "4_4") (pintype "passive"))
    )
    (net (code "54") (name "Net-(G1-In-)") (class "Default")
      (node (ref "C54") (pin "2") (pinfunction "2_2") (pintype "passive"))
      (node (ref "G1") (pin "1") (pinfunction "In-_1") (pintype "passive"))
      (node (ref "L7") (pin "3") (pinfunction "3_3") (pintype "passive"))
    )
    (net (code "55") (name "Net-(G1-Out+)") (class "Default")
      (node (ref "G1") (pin "6") (pinfunction "Out+_6") (pintype "passive"))
      (node (ref "VD18") (pin "1") (pinfunction "A_1") (pintype "passive"))
    )
    (net (code "56") (name "Net-(G2-In+)") (class "Default")
      (node (ref "C61") (pin "2") (pinfunction "2_2") (pintype "passive"))
      (node (ref "G2") (pin "2") (pinfunction "In+_2") (pintype "passive"))
      (node (ref "L8") (pin "2") (pinfunction "2_2") (pintype "passive"))
    )
    (net (code "57") (name "Net-(VD7-A)") (class "Default")
      (node (ref "VD7") (pin "1") (pinfunction "A_1") (pintype "passive"))
      (node (ref "XP1") (pin "7") (pinfunction "7_7") (pintype "passive"))
      (node (ref "XP1") (pin "8") (pinfunction "8_8") (pintype "passive"))
    )
    (net (code "58") (name "Net-(VD8-A)") (class "Default")
      (node (ref "VD8") (pin "1") (pinfunction "A_1") (pintype "passive"))
      (node (ref "XP1") (pin "10") (pinfunction "10_10") (pintype "passive"))
      (node (ref "XP1") (pin "9") (pinfunction "9_9") (pintype "passive"))
    )
    (net (code "59") (name "Net-(VD11-K1)") (class "Default")
      (node (ref "R58") (pin "1") (pinfunction "1_1") (pintype "passive"))
      (node (ref "VD11") (pin "1") (pinfunction "K1_1") (pintype "passive"))
    )
    (net (code "60") (name "Net-(VD11-K2)") (class "Default")
      (node (ref "R57") (pin "1") (pinfunction "1_1") (pintype "passive"))
      (node (ref "VD11") (pin "3") (pinfunction "K2_3") (pintype "passive"))
    )
    (net (code "61") (name "Net-(VD12-A)") (class "Default")
      (node (ref "VD12") (pin "1") (pinfunction "A_1") (pintype "passive"))
      (node (ref "XS6") (pin "1") (pinfunction "+Vcc_1") (pintype "passive"))
    )
    (net (code "62") (name "Net-(VD13-K)") (class "Default")
      (node (ref "R60") (pin "2") (pinfunction "2_2") (pintype "passive"))
      (node (ref "VD13") (pin "2") (pinfunction "K_2") (pintype "passive"))
    )
    (net (code "63") (name "Net-(VD15-K)") (class "Default")
      (node (ref "L5") (pin "1") (pinfunction "1_1") (pintype "passive"))
      (node (ref "VD15") (pin "2") (pinfunction "K_2") (pintype "passive"))
    )
    (net (code "64") (name "Net-(VD16-K)") (class "Default")
      (node (ref "R63") (pin "2") (pinfunction "2_2") (pintype "passive"))
      (node (ref "VD16") (pin "2") (pinfunction "K_2") (pintype "passive"))
    )
    (net (code "65") (name "Net-(VD17-A)") (class "Default")
      (node (ref "C56") (pin "1") (pinfunction "1_1") (pintype "passive"))
      (node (ref "C57") (pin "1") (pinfunction "1_1") (pintype "passive"))
      (node (ref "L6") (pin "2") (pinfunction "2_2") (pintype "passive"))
      (node (ref "L7") (pin "2") (pinfunction "2_2") (pintype "passive"))
      (node (ref "VD17") (pin "1") (pinfunction "A_1") (pintype "passive"))
    )
    (net (code "66") (name "Net-(VD17-K)") (class "Default")
      (node (ref "C56") (pin "2") (pinfunction "2_2") (pintype "passive"))
      (node (ref "C57") (pin "2") (pinfunction "2_2") (pintype "passive"))
      (node (ref "L5") (pin "2") (pinfunction "2_2") (pintype "passive"))
      (node (ref "L7") (pin "1") (pinfunction "1_1") (pintype "passive"))
      (node (ref "VD17") (pin "2") (pinfunction "K_2") (pintype "passive"))
      (node (ref "VD22") (pin "1") (pinfunction "A_1") (pintype "passive"))
    )
    (net (code "67") (name "Net-(VD22-K)") (class "Default")
      (node (ref "R65") (pin "2") (pinfunction "2_2") (pintype "passive"))
      (node (ref "VD22") (pin "2") (pinfunction "K_2") (pintype "passive"))
    )
    (net (code "68") (name "Net-(VT1-B)") (class "Default")
      (node (ref "R53") (pin "1") (pinfunction "1_1") (pintype "passive"))
      (node (ref "R54") (pin "2") (pinfunction "2_2") (pintype "passive"))
      (node (ref "R55") (pin "2") (pinfunction "2_2") (pintype "passive"))
      (node (ref "VT1") (pin "1") (pinfunction "B_1") (pintype "passive"))
    )
    (net (code "69") (name "Net-(VT1-E)") (class "Default")
      (node (ref "R56") (pin "1") (pinfunction "1_1") (pintype "passive"))
      (node (ref "VT1") (pin "2") (pinfunction "E_2") (pintype "passive"))
    )
    (net (code "70") (name "Net-(VT2-D)") (class "Default")
      (node (ref "R57") (pin "2") (pinfunction "2_2") (pintype "passive"))
      (node (ref "VT2") (pin "3") (pinfunction "D_3") (pintype "passive"))
    )
    (net (code "71") (name "Net-(VT2-G)") (class "Default")
      (node (ref "R61") (pin "2") (pinfunction "2_2") (pintype "passive"))
      (node (ref "VT2") (pin "1") (pinfunction "G_1") (pintype "passive"))
    )
    (net (code "72") (name "Net-(VT3-D)") (class "Default")
      (node (ref "R58") (pin "2") (pinfunction "2_2") (pintype "passive"))
      (node (ref "VT3") (pin "3") (pinfunction "D_3") (pintype "passive"))
    )
    (net (code "73") (name "Net-(VT3-G)") (class "Default")
      (node (ref "R62") (pin "1") (pinfunction "1_1") (pintype "passive"))
      (node (ref "VT3") (pin "1") (pinfunction "G_1") (pintype "passive"))
    )
    (net (code "74") (name "Net-(XS6-D+)") (class "Default")
      (node (ref "DA3") (pin "3") (pinfunction "I/O2_3") (pintype "passive"))
      (node (ref "R56") (pin "2") (pinfunction "2_2") (pintype "passive"))
      (node (ref "XS6") (pin "3") (pinfunction "D+_3") (pintype "passive"))
    )
    (net (code "75") (name "Net-(XS6-D-)") (class "Default")
      (node (ref "DA3") (pin "1") (pinfunction "I/O1_1") (pintype "passive"))
      (node (ref "XS6") (pin "2") (pinfunction "D-_2") (pintype "passive"))
    )
    (net (code "76") (name "Net-(XS6-SHL1)") (class "Default")
      (node (ref "C45") (pin "1") (pinfunction "1_1") (pintype "passive"))
      (node (ref "XS6") (pin "5") (pinfunction "SHL1_5") (pintype "passive"))
      (node (ref "XS6") (pin "6") (pinfunction "SHL2_6") (pintype "passive"))
    )
    (net (code "77") (name "unconnected-(DD1-PB5-Pad41)") (class "Default")
      (node (ref "DD1") (pin "41") (pinfunction "PB5_41") (pintype "passive"))
    )
    (net (code "78") (name "unconnected-(DD1-PB8-Pad45)") (class "Default")
      (node (ref "DD1") (pin "45") (pinfunction "PB8_45") (pintype "passive"))
    )
    (net (code "79") (name "unconnected-(DD1-PB9-Pad46)") (class "Default")
      (node (ref "DD1") (pin "46") (pinfunction "PB9_46") (pintype "passive"))
    )
    (net (code "80") (name "unconnected-(G1-CS-Pad8)") (class "Default")
      (node (ref "G1") (pin "8") (pinfunction "CS_8") (pintype "passive"))
    )
    (net (code "81") (name "unconnected-(G1-ctrl-Pad3)") (class "Default")
      (node (ref "G1") (pin "3") (pinfunction "ctrl_3") (pintype "passive"))
    )
    (net (code "82") (name "unconnected-(XP1-Pad3)") (class "Default")
      (node (ref "XP1") (pin "3") (pinfunction "3_3") (pintype "passive"))
    )
  )
)
